# Motherboard_simple.net
KiCad netlist of a schematic drawn in EAGLE
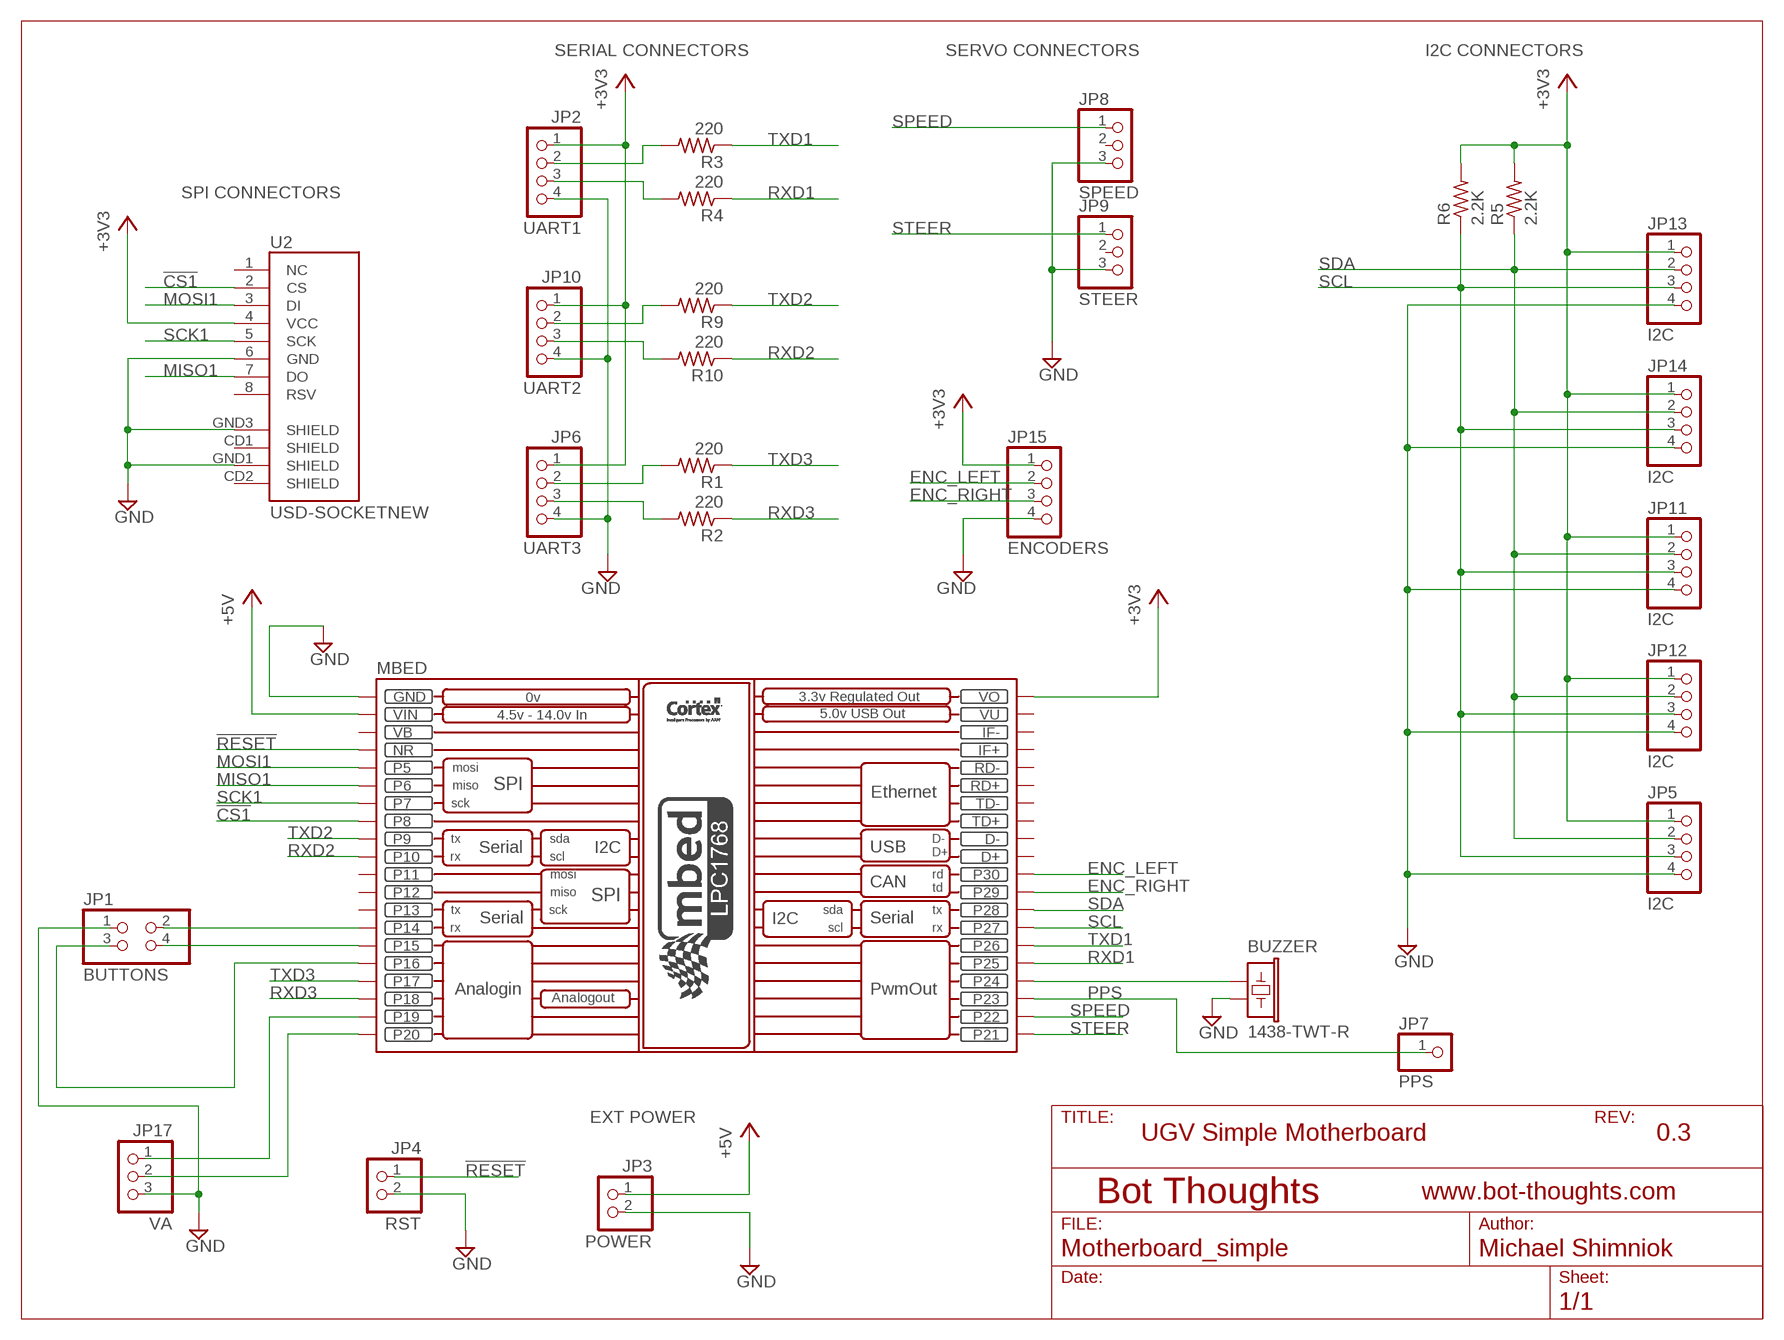
[diagram p0: schematic, sheet 1]

(export (version "E")
  (design (tool "Eeschema 10.0.6"))
  (components
    (comp (ref "BUZZER")
      (value "1438-TWT-R")
      (footprint "eagle-import:BUZZER_14MM_PTH")
      (fields (field (name "MF") "PROJECTS UNLIMITED") (field (name "MPN") "AT-1438-TWT-R"))
      (libsource (lib "eagle-import") (part "BUZZER-AT-1438-TWT-R"))
    )
    (comp (ref "JP1")
      (value "BUTTONS")
      (footprint "eagle-import:2X02")
      (libsource (lib "eagle-import") (part "PINHD-2X02_2.54"))
    )
    (comp (ref "JP2")
      (value "UART1")
      (footprint "eagle-import:1X04-S")
      (libsource (lib "eagle-import") (part "PINHD-1X04_2.54-S"))
    )
    (comp (ref "JP3")
      (value "POWER")
      (footprint "eagle-import:1X02_90-S")
      (libsource (lib "eagle-import") (part "PINHD-1X02_2.54-90°-S"))
    )
    (comp (ref "JP4")
      (value "RST")
      (footprint "eagle-import:1X02-S")
      (libsource (lib "eagle-import") (part "PINHD-1X02_2.54-S"))
    )
    (comp (ref "JP5")
      (value "I2C")
      (footprint "eagle-import:1X04-S")
      (libsource (lib "eagle-import") (part "PINHD-1X04_2.54-S"))
    )
    (comp (ref "JP6")
      (value "UART3")
      (footprint "eagle-import:1X04-S")
      (libsource (lib "eagle-import") (part "PINHD-1X04_2.54-S"))
    )
    (comp (ref "JP7")
      (value "PPS")
      (footprint "eagle-import:1X01-S")
      (libsource (lib "eagle-import") (part "PINHD-1X01_2.54-S"))
    )
    (comp (ref "JP8")
      (value "SPEED")
      (footprint "eagle-import:1X03-S")
      (libsource (lib "eagle-import") (part "PINHD-1X03_2.54-S"))
    )
    (comp (ref "JP9")
      (value "STEER")
      (footprint "eagle-import:1X03-S")
      (libsource (lib "eagle-import") (part "PINHD-1X03_2.54-S"))
    )
    (comp (ref "JP10")
      (value "UART2")
      (footprint "eagle-import:1X04-S")
      (libsource (lib "eagle-import") (part "PINHD-1X04_2.54-S"))
    )
    (comp (ref "JP11")
      (value "I2C")
      (footprint "eagle-import:1X04-S")
      (libsource (lib "eagle-import") (part "PINHD-1X04_2.54-S"))
    )
    (comp (ref "JP12")
      (value "I2C")
      (footprint "eagle-import:1X04-S")
      (libsource (lib "eagle-import") (part "PINHD-1X04_2.54-S"))
    )
    (comp (ref "JP13")
      (value "I2C")
      (footprint "eagle-import:1X04-S")
      (libsource (lib "eagle-import") (part "PINHD-1X04_2.54-S"))
    )
    (comp (ref "JP14")
      (value "I2C")
      (footprint "eagle-import:1X04-S")
      (libsource (lib "eagle-import") (part "PINHD-1X04_2.54-S"))
    )
    (comp (ref "JP15")
      (value "ENCODERS")
      (footprint "eagle-import:1X04-S")
      (libsource (lib "eagle-import") (part "PINHD-1X04_2.54-S"))
    )
    (comp (ref "JP17")
      (value "VA")
      (footprint "eagle-import:1X03-S")
      (libsource (lib "eagle-import") (part "PINHD-1X03_2.54-S"))
    )
    (comp (ref "MBED")
      (value "MBED_NXP_LPC1768")
      (footprint "eagle-import:MBED-KIT")
      (fields (field (name "MPN") "2212S-20SG-85"))
      (libsource (lib "eagle-import") (part "MBED_NXP_LPC1768"))
    )
    (comp (ref "R1")
      (value "220")
      (footprint "eagle-import:0204_5")
      (fields (field (name "MPN") "WCR0805-220RFI"))
      (libsource (lib "eagle-import") (part "R-US_0204/5"))
    )
    (comp (ref "R2")
      (value "220")
      (footprint "eagle-import:0204_5")
      (fields (field (name "MPN") "WCR0805-220RFI"))
      (libsource (lib "eagle-import") (part "R-US_0204/5"))
    )
    (comp (ref "R3")
      (value "220")
      (footprint "eagle-import:0204_5")
      (fields (field (name "MPN") "WCR0805-220RFI"))
      (libsource (lib "eagle-import") (part "R-US_0204/5"))
    )
    (comp (ref "R4")
      (value "220")
      (footprint "eagle-import:0204_5")
      (fields (field (name "MPN") "WCR0805-220RFI"))
      (libsource (lib "eagle-import") (part "R-US_0204/5"))
    )
    (comp (ref "R5")
      (value "2.2K")
      (footprint "eagle-import:0204_5")
      (libsource (lib "eagle-import") (part "R-US_0204/5"))
    )
    (comp (ref "R6")
      (value "2.2K")
      (footprint "eagle-import:0204_5")
      (libsource (lib "eagle-import") (part "R-US_0204/5"))
    )
    (comp (ref "R9")
      (value "220")
      (footprint "eagle-import:0204_5")
      (fields (field (name "MPN") "WCR0805-220RFI"))
      (libsource (lib "eagle-import") (part "R-US_0204/5"))
    )
    (comp (ref "R10")
      (value "220")
      (footprint "eagle-import:0204_5")
      (fields (field (name "MPN") "WCR0805-220RFI"))
      (libsource (lib "eagle-import") (part "R-US_0204/5"))
    )
    (comp (ref "U2")
      (value "USD-SOCKETNEW")
      (footprint "eagle-import:MICRO-SD-SOCKET-PP")
      (libsource (lib "eagle-import") (part "USD-SOCKETNEW"))
    )
  )
  (nets
    (net (code "1") (name "+3V3") (class "Default")
      (node (ref "JP10") (pin "1") (pinfunction "1_1") (pintype "passive"))
      (node (ref "JP11") (pin "1") (pinfunction "1_1") (pintype "passive"))
      (node (ref "JP12") (pin "1") (pinfunction "1_1") (pintype "passive"))
      (node (ref "JP13") (pin "1") (pinfunction "1_1") (pintype "passive"))
      (node (ref "JP14") (pin "1") (pinfunction "1_1") (pintype "passive"))
      (node (ref "JP15") (pin "1") (pinfunction "1_1") (pintype "passive"))
      (node (ref "JP2") (pin "1") (pinfunction "1_1") (pintype "passive"))
      (node (ref "JP5") (pin "1") (pinfunction "1_1") (pintype "passive"))
      (node (ref "JP6") (pin "1") (pinfunction "1_1") (pintype "passive"))
      (node (ref "MBED") (pin "VOUT") (pinfunction "VO_VOUT") (pintype "power_in"))
      (node (ref "R5") (pin "2") (pinfunction "2_2") (pintype "passive"))
      (node (ref "R6") (pin "2") (pinfunction "2_2") (pintype "passive"))
      (node (ref "U2") (pin "4") (pinfunction "VCC_4") (pintype "bidirectional"))
    )
    (net (code "2") (name "+5V") (class "Default")
      (node (ref "JP3") (pin "1") (pinfunction "1_1") (pintype "passive"))
      (node (ref "MBED") (pin "VIN") (pinfunction "VIN_VIN") (pintype "power_in"))
    )
    (net (code "3") (name "/ENC_LEFT") (class "Default")
      (node (ref "JP15") (pin "2") (pinfunction "2_2") (pintype "passive"))
      (node (ref "MBED") (pin "P$30") (pinfunction "P30_P$30") (pintype "bidirectional"))
    )
    (net (code "4") (name "/ENC_RIGHT") (class "Default")
      (node (ref "JP15") (pin "3") (pinfunction "3_3") (pintype "passive"))
      (node (ref "MBED") (pin "P$29") (pinfunction "P29_P$29") (pintype "bidirectional"))
    )
    (net (code "5") (name "/MISO1") (class "Default")
      (node (ref "MBED") (pin "P$6") (pinfunction "P6_P$6") (pintype "bidirectional"))
      (node (ref "U2") (pin "7") (pinfunction "DO_7") (pintype "bidirectional"))
    )
    (net (code "6") (name "/MOSI1") (class "Default")
      (node (ref "MBED") (pin "P$5") (pinfunction "P5_P$5") (pintype "bidirectional"))
      (node (ref "U2") (pin "3") (pinfunction "DI_3") (pintype "bidirectional"))
    )
    (net (code "7") (name "/PPS") (class "Default")
      (node (ref "JP7") (pin "1") (pinfunction "1_1") (pintype "passive"))
      (node (ref "MBED") (pin "P$23") (pinfunction "P23_P$23") (pintype "bidirectional"))
    )
    (net (code "8") (name "/RXD1") (class "Default")
      (node (ref "MBED") (pin "P$25") (pinfunction "P25_P$25") (pintype "bidirectional"))
      (node (ref "R4") (pin "1") (pinfunction "1_1") (pintype "passive"))
    )
    (net (code "9") (name "/RXD2") (class "Default")
      (node (ref "MBED") (pin "P$10") (pinfunction "P10_P$10") (pintype "bidirectional"))
      (node (ref "R10") (pin "1") (pinfunction "1_1") (pintype "passive"))
    )
    (net (code "10") (name "/RXD3") (class "Default")
      (node (ref "MBED") (pin "P$18") (pinfunction "P18_P$18") (pintype "bidirectional"))
      (node (ref "R2") (pin "1") (pinfunction "1_1") (pintype "passive"))
    )
    (net (code "11") (name "/SCK1") (class "Default")
      (node (ref "MBED") (pin "P$7") (pinfunction "P7_P$7") (pintype "bidirectional"))
      (node (ref "U2") (pin "5") (pinfunction "SCK_5") (pintype "bidirectional"))
    )
    (net (code "12") (name "/SCL") (class "Default")
      (node (ref "JP11") (pin "3") (pinfunction "3_3") (pintype "passive"))
      (node (ref "JP12") (pin "3") (pinfunction "3_3") (pintype "passive"))
      (node (ref "JP13") (pin "3") (pinfunction "3_3") (pintype "passive"))
      (node (ref "JP14") (pin "3") (pinfunction "3_3") (pintype "passive"))
      (node (ref "JP5") (pin "3") (pinfunction "3_3") (pintype "passive"))
      (node (ref "MBED") (pin "P$27") (pinfunction "P27_P$27") (pintype "bidirectional"))
      (node (ref "R6") (pin "1") (pinfunction "1_1") (pintype "passive"))
    )
    (net (code "13") (name "/SDA") (class "Default")
      (node (ref "JP11") (pin "2") (pinfunction "2_2") (pintype "passive"))
      (node (ref "JP12") (pin "2") (pinfunction "2_2") (pintype "passive"))
      (node (ref "JP13") (pin "2") (pinfunction "2_2") (pintype "passive"))
      (node (ref "JP14") (pin "2") (pinfunction "2_2") (pintype "passive"))
      (node (ref "JP5") (pin "2") (pinfunction "2_2") (pintype "passive"))
      (node (ref "MBED") (pin "P$28") (pinfunction "P28_P$28") (pintype "bidirectional"))
      (node (ref "R5") (pin "1") (pinfunction "1_1") (pintype "passive"))
    )
    (net (code "14") (name "/SPEED") (class "Default")
      (node (ref "JP8") (pin "1") (pinfunction "1_1") (pintype "passive"))
      (node (ref "MBED") (pin "P$22") (pinfunction "P22_P$22") (pintype "bidirectional"))
    )
    (net (code "15") (name "/STEER") (class "Default")
      (node (ref "JP9") (pin "1") (pinfunction "1_1") (pintype "passive"))
      (node (ref "MBED") (pin "P$21") (pinfunction "P21_P$21") (pintype "bidirectional"))
    )
    (net (code "16") (name "/TXD1") (class "Default")
      (node (ref "MBED") (pin "P$26") (pinfunction "P26_P$26") (pintype "bidirectional"))
      (node (ref "R3") (pin "1") (pinfunction "1_1") (pintype "passive"))
    )
    (net (code "17") (name "/TXD2") (class "Default")
      (node (ref "MBED") (pin "P$9") (pinfunction "P9_P$9") (pintype "bidirectional"))
      (node (ref "R9") (pin "1") (pinfunction "1_1") (pintype "passive"))
    )
    (net (code "18") (name "/TXD3") (class "Default")
      (node (ref "MBED") (pin "P$17") (pinfunction "P17_P$17") (pintype "bidirectional"))
      (node (ref "R1") (pin "1") (pinfunction "1_1") (pintype "passive"))
    )
    (net (code "19") (name "/VB") (class "Default")
      (node (ref "MBED") (pin "VB") (pinfunction "VB_VB") (pintype "power_in"))
    )
    (net (code "20") (name "/VU") (class "Default")
      (node (ref "MBED") (pin "VU") (pinfunction "VU_VU") (pintype "power_in"))
    )
    (net (code "21") (name "/~{CS1}") (class "Default")
      (node (ref "MBED") (pin "P$8") (pinfunction "P8_P$8") (pintype "bidirectional"))
      (node (ref "U2") (pin "2") (pinfunction "CS_2") (pintype "bidirectional"))
    )
    (net (code "22") (name "/~{RESET}") (class "Default")
      (node (ref "JP4") (pin "1") (pinfunction "1_1") (pintype "passive"))
      (node (ref "MBED") (pin "NR") (pinfunction "NR_NR") (pintype "power_in"))
    )
    (net (code "23") (name "GND") (class "Default")
      (node (ref "BUZZER") (pin "P$2") (pinfunction "2_P$2") (pintype "passive"))
      (node (ref "JP1") (pin "1") (pinfunction "1_1") (pintype "passive"))
      (node (ref "JP10") (pin "4") (pinfunction "4_4") (pintype "passive"))
      (node (ref "JP11") (pin "4") (pinfunction "4_4") (pintype "passive"))
      (node (ref "JP12") (pin "4") (pinfunction "4_4") (pintype "passive"))
      (node (ref "JP13") (pin "4") (pinfunction "4_4") (pintype "passive"))
      (node (ref "JP14") (pin "4") (pinfunction "4_4") (pintype "passive"))
      (node (ref "JP15") (pin "4") (pinfunction "4_4") (pintype "passive"))
      (node (ref "JP17") (pin "3") (pinfunction "3_3") (pintype "passive"))
      (node (ref "JP2") (pin "4") (pinfunction "4_4") (pintype "passive"))
      (node (ref "JP3") (pin "2") (pinfunction "2_2") (pintype "passive"))
      (node (ref "JP4") (pin "2") (pinfunction "2_2") (pintype "passive"))
      (node (ref "JP5") (pin "4") (pinfunction "4_4") (pintype "passive"))
      (node (ref "JP6") (pin "4") (pinfunction "4_4") (pintype "passive"))
      (node (ref "JP8") (pin "3") (pinfunction "3_3") (pintype "passive"))
      (node (ref "JP9") (pin "3") (pinfunction "3_3") (pintype "passive"))
      (node (ref "MBED") (pin "GND") (pinfunction "GND_GND") (pintype "power_in"))
      (node (ref "U2") (pin "6") (pinfunction "GND_6") (pintype "bidirectional"))
      (node (ref "U2") (pin "GND1") (pinfunction "SHIELD_GND1") (pintype "bidirectional"))
      (node (ref "U2") (pin "GND3") (pinfunction "SHIELD_GND3") (pintype "bidirectional"))
    )
    (net (code "24") (name "Net-(BUZZER-1)") (class "Default")
      (node (ref "BUZZER") (pin "P$1") (pinfunction "1_P$1") (pintype "passive"))
      (node (ref "MBED") (pin "P$24") (pinfunction "P24_P$24") (pintype "bidirectional"))
    )
    (net (code "25") (name "Net-(JP2-Pad2)") (class "Default")
      (node (ref "JP2") (pin "2") (pinfunction "2_2") (pintype "passive"))
      (node (ref "R3") (pin "2") (pinfunction "2_2") (pintype "passive"))
    )
    (net (code "26") (name "Net-(JP2-Pad3)") (class "Default")
      (node (ref "JP2") (pin "3") (pinfunction "3_3") (pintype "passive"))
      (node (ref "R4") (pin "2") (pinfunction "2_2") (pintype "passive"))
    )
    (net (code "27") (name "Net-(JP6-Pad2)") (class "Default")
      (node (ref "JP6") (pin "2") (pinfunction "2_2") (pintype "passive"))
      (node (ref "R1") (pin "2") (pinfunction "2_2") (pintype "passive"))
    )
    (net (code "28") (name "Net-(JP6-Pad3)") (class "Default")
      (node (ref "JP6") (pin "3") (pinfunction "3_3") (pintype "passive"))
      (node (ref "R2") (pin "2") (pinfunction "2_2") (pintype "passive"))
    )
    (net (code "29") (name "Net-(JP10-Pad2)") (class "Default")
      (node (ref "JP10") (pin "2") (pinfunction "2_2") (pintype "passive"))
      (node (ref "R9") (pin "2") (pinfunction "2_2") (pintype "passive"))
    )
    (net (code "30") (name "Net-(JP10-Pad3)") (class "Default")
      (node (ref "JP10") (pin "3") (pinfunction "3_3") (pintype "passive"))
      (node (ref "R10") (pin "2") (pinfunction "2_2") (pintype "passive"))
    )
    (net (code "31") (name "Net-(MBED-P14)") (class "Default")
      (node (ref "JP1") (pin "2") (pinfunction "2_2") (pintype "passive"))
      (node (ref "MBED") (pin "P$14") (pinfunction "P14_P$14") (pintype "bidirectional"))
    )
    (net (code "32") (name "Net-(MBED-P15)") (class "Default")
      (node (ref "JP1") (pin "4") (pinfunction "4_4") (pintype "passive"))
      (node (ref "MBED") (pin "P$15") (pinfunction "P15_P$15") (pintype "bidirectional"))
    )
    (net (code "33") (name "Net-(MBED-P16)") (class "Default")
      (node (ref "JP1") (pin "3") (pinfunction "3_3") (pintype "passive"))
      (node (ref "MBED") (pin "P$16") (pinfunction "P16_P$16") (pintype "bidirectional"))
    )
    (net (code "34") (name "Net-(MBED-P19)") (class "Default")
      (node (ref "JP17") (pin "1") (pinfunction "1_1") (pintype "passive"))
      (node (ref "MBED") (pin "P$19") (pinfunction "P19_P$19") (pintype "bidirectional"))
    )
    (net (code "35") (name "Net-(MBED-P20)") (class "Default")
      (node (ref "JP17") (pin "2") (pinfunction "2_2") (pintype "passive"))
      (node (ref "MBED") (pin "P$20") (pinfunction "P20_P$20") (pintype "bidirectional"))
    )
    (net (code "36") (name "unconnected-(JP8-Pad2)") (class "Default")
      (node (ref "JP8") (pin "2") (pinfunction "2_2") (pintype "passive"))
    )
    (net (code "37") (name "unconnected-(JP9-Pad2)") (class "Default")
      (node (ref "JP9") (pin "2") (pinfunction "2_2") (pintype "passive"))
    )
    (net (code "38") (name "unconnected-(MBED-P11-PadP$11)") (class "Default")
      (node (ref "MBED") (pin "P$11") (pinfunction "P11_P$11") (pintype "bidirectional"))
    )
    (net (code "39") (name "unconnected-(MBED-P12-PadP$12)") (class "Default")
      (node (ref "MBED") (pin "P$12") (pinfunction "P12_P$12") (pintype "bidirectional"))
    )
    (net (code "40") (name "unconnected-(MBED-P13-PadP$13)") (class "Default")
      (node (ref "MBED") (pin "P$13") (pinfunction "P13_P$13") (pintype "bidirectional"))
    )
    (net (code "41") (name "unconnected-(MBED-PadD+)") (class "Default")
      (node (ref "MBED") (pin "D+") (pinfunction "D+_D+") (pintype "bidirectional"))
    )
    (net (code "42") (name "unconnected-(MBED-PadD-)") (class "Default")
      (node (ref "MBED") (pin "D-") (pinfunction "D-_D-") (pintype "bidirectional"))
    )
    (net (code "43") (name "unconnected-(MBED-PadIF+)") (class "Default")
      (node (ref "MBED") (pin "IF+") (pinfunction "IF+_IF+") (pintype "bidirectional"))
    )
    (net (code "44") (name "unconnected-(MBED-PadIF-)") (class "Default")
      (node (ref "MBED") (pin "IF-") (pinfunction "IF-_IF-") (pintype "bidirectional"))
    )
    (net (code "45") (name "unconnected-(MBED-PadRD+)") (class "Default")
      (node (ref "MBED") (pin "RD+") (pinfunction "RD+_RD+") (pintype "bidirectional"))
    )
    (net (code "46") (name "unconnected-(MBED-PadRD-)") (class "Default")
      (node (ref "MBED") (pin "RD-") (pinfunction "RD-_RD-") (pintype "bidirectional"))
    )
    (net (code "47") (name "unconnected-(MBED-PadTD+)") (class "Default")
      (node (ref "MBED") (pin "TD+") (pinfunction "TD+_TD+") (pintype "bidirectional"))
    )
    (net (code "48") (name "unconnected-(MBED-PadTD-)") (class "Default")
      (node (ref "MBED") (pin "TD-") (pinfunction "TD-_TD-") (pintype "bidirectional"))
    )
    (net (code "49") (name "unconnected-(U2-NC-Pad1)") (class "Default")
      (node (ref "U2") (pin "1") (pinfunction "NC_1") (pintype "bidirectional"))
    )
    (net (code "50") (name "unconnected-(U2-RSV-Pad8)") (class "Default")
      (node (ref "U2") (pin "8") (pinfunction "RSV_8") (pintype "bidirectional"))
    )
    (net (code "51") (name "unconnected-(U2-SHIELD-PadCD1)") (class "Default")
      (node (ref "U2") (pin "CD1") (pinfunction "SHIELD_CD1") (pintype "bidirectional"))
    )
    (net (code "52") (name "unconnected-(U2-SHIELD-PadCD2)") (class "Default")
      (node (ref "U2") (pin "CD2") (pinfunction "SHIELD_CD2") (pintype "bidirectional"))
    )
  )
)
